# CNC-PowerSwitch-2016-v0_9.net
KiCad netlist of a schematic drawn in EAGLE
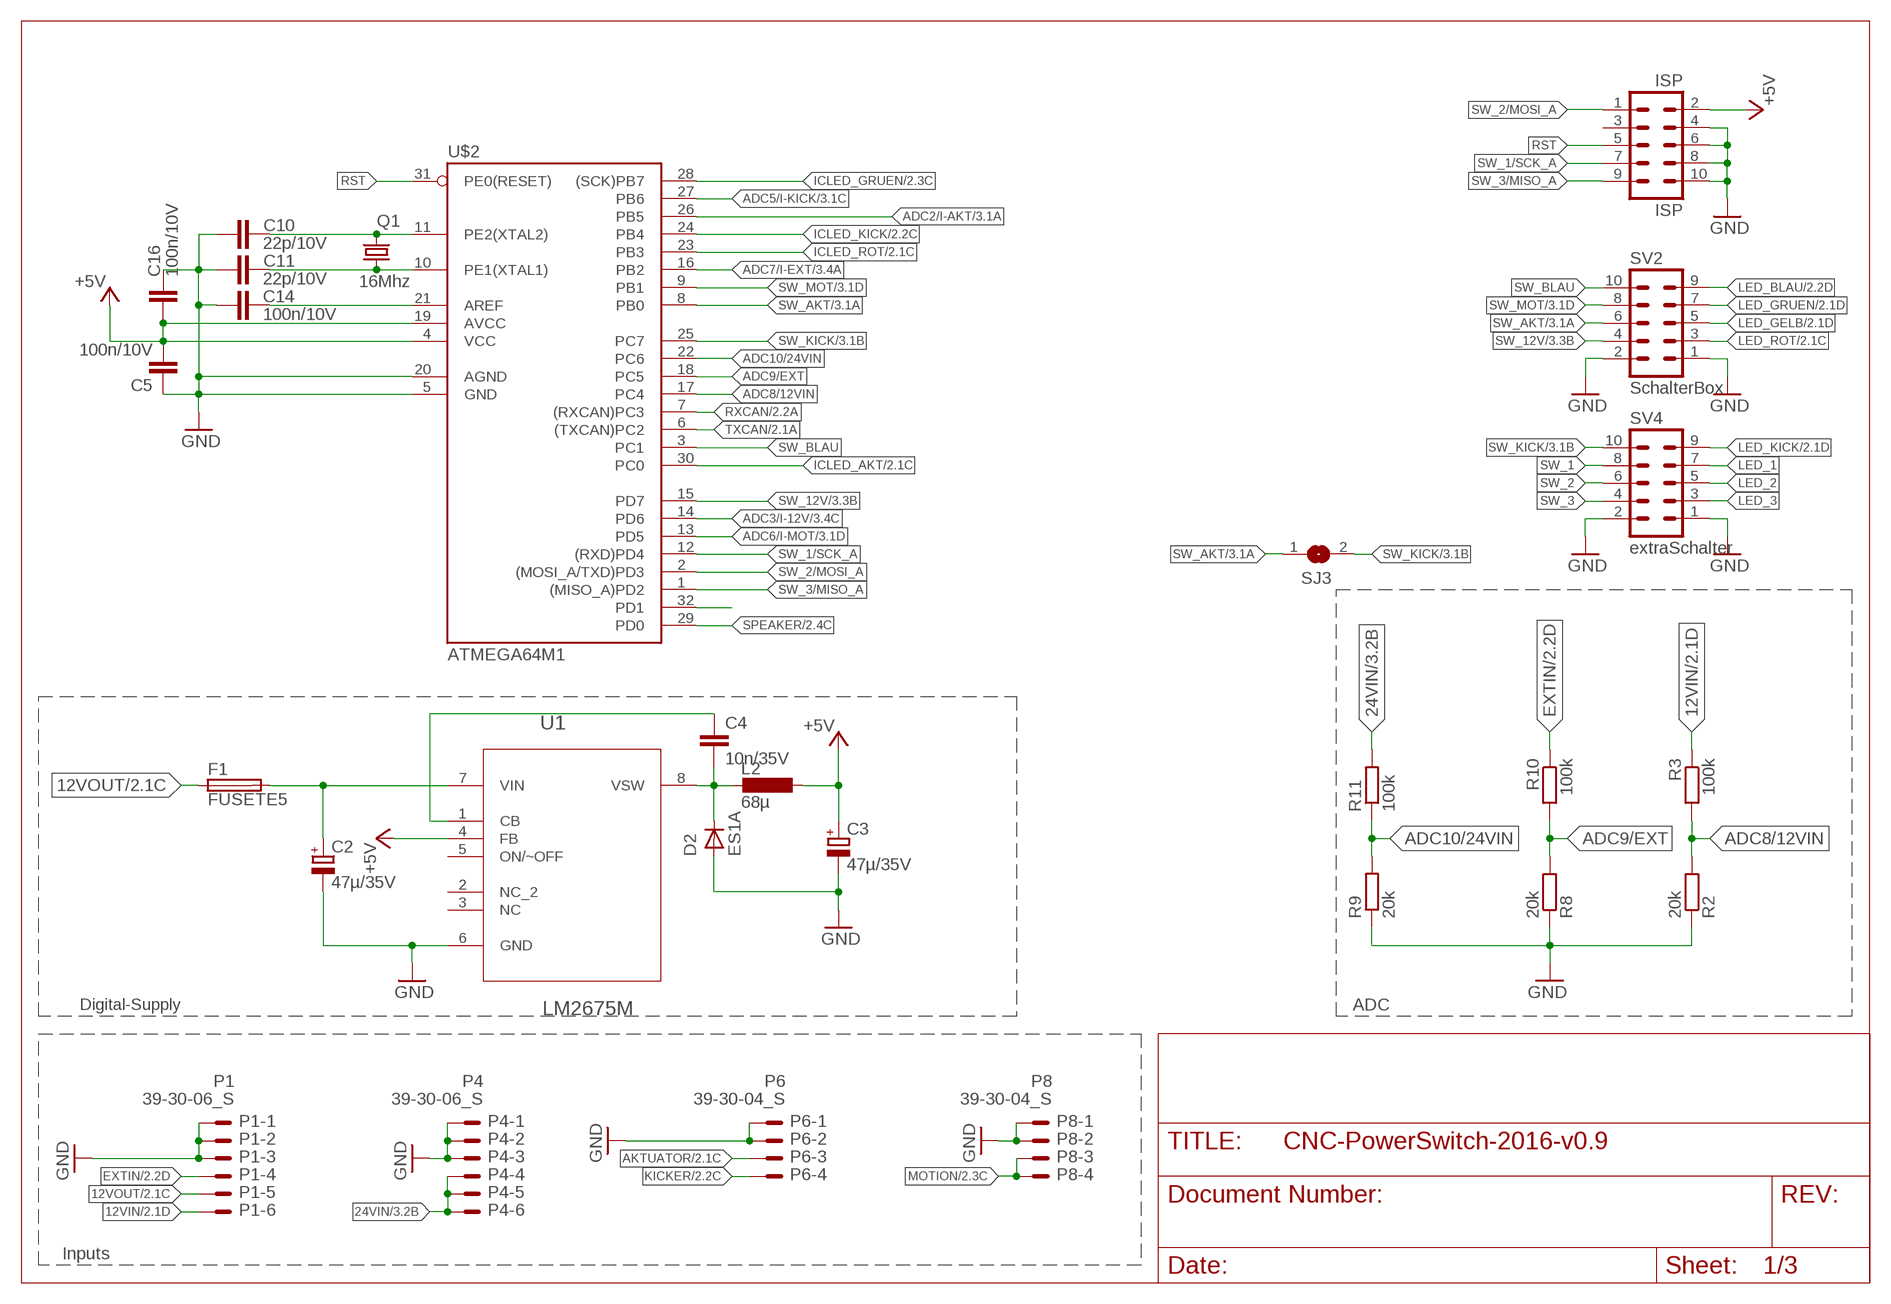
[diagram p0: schematic, sheet 1]
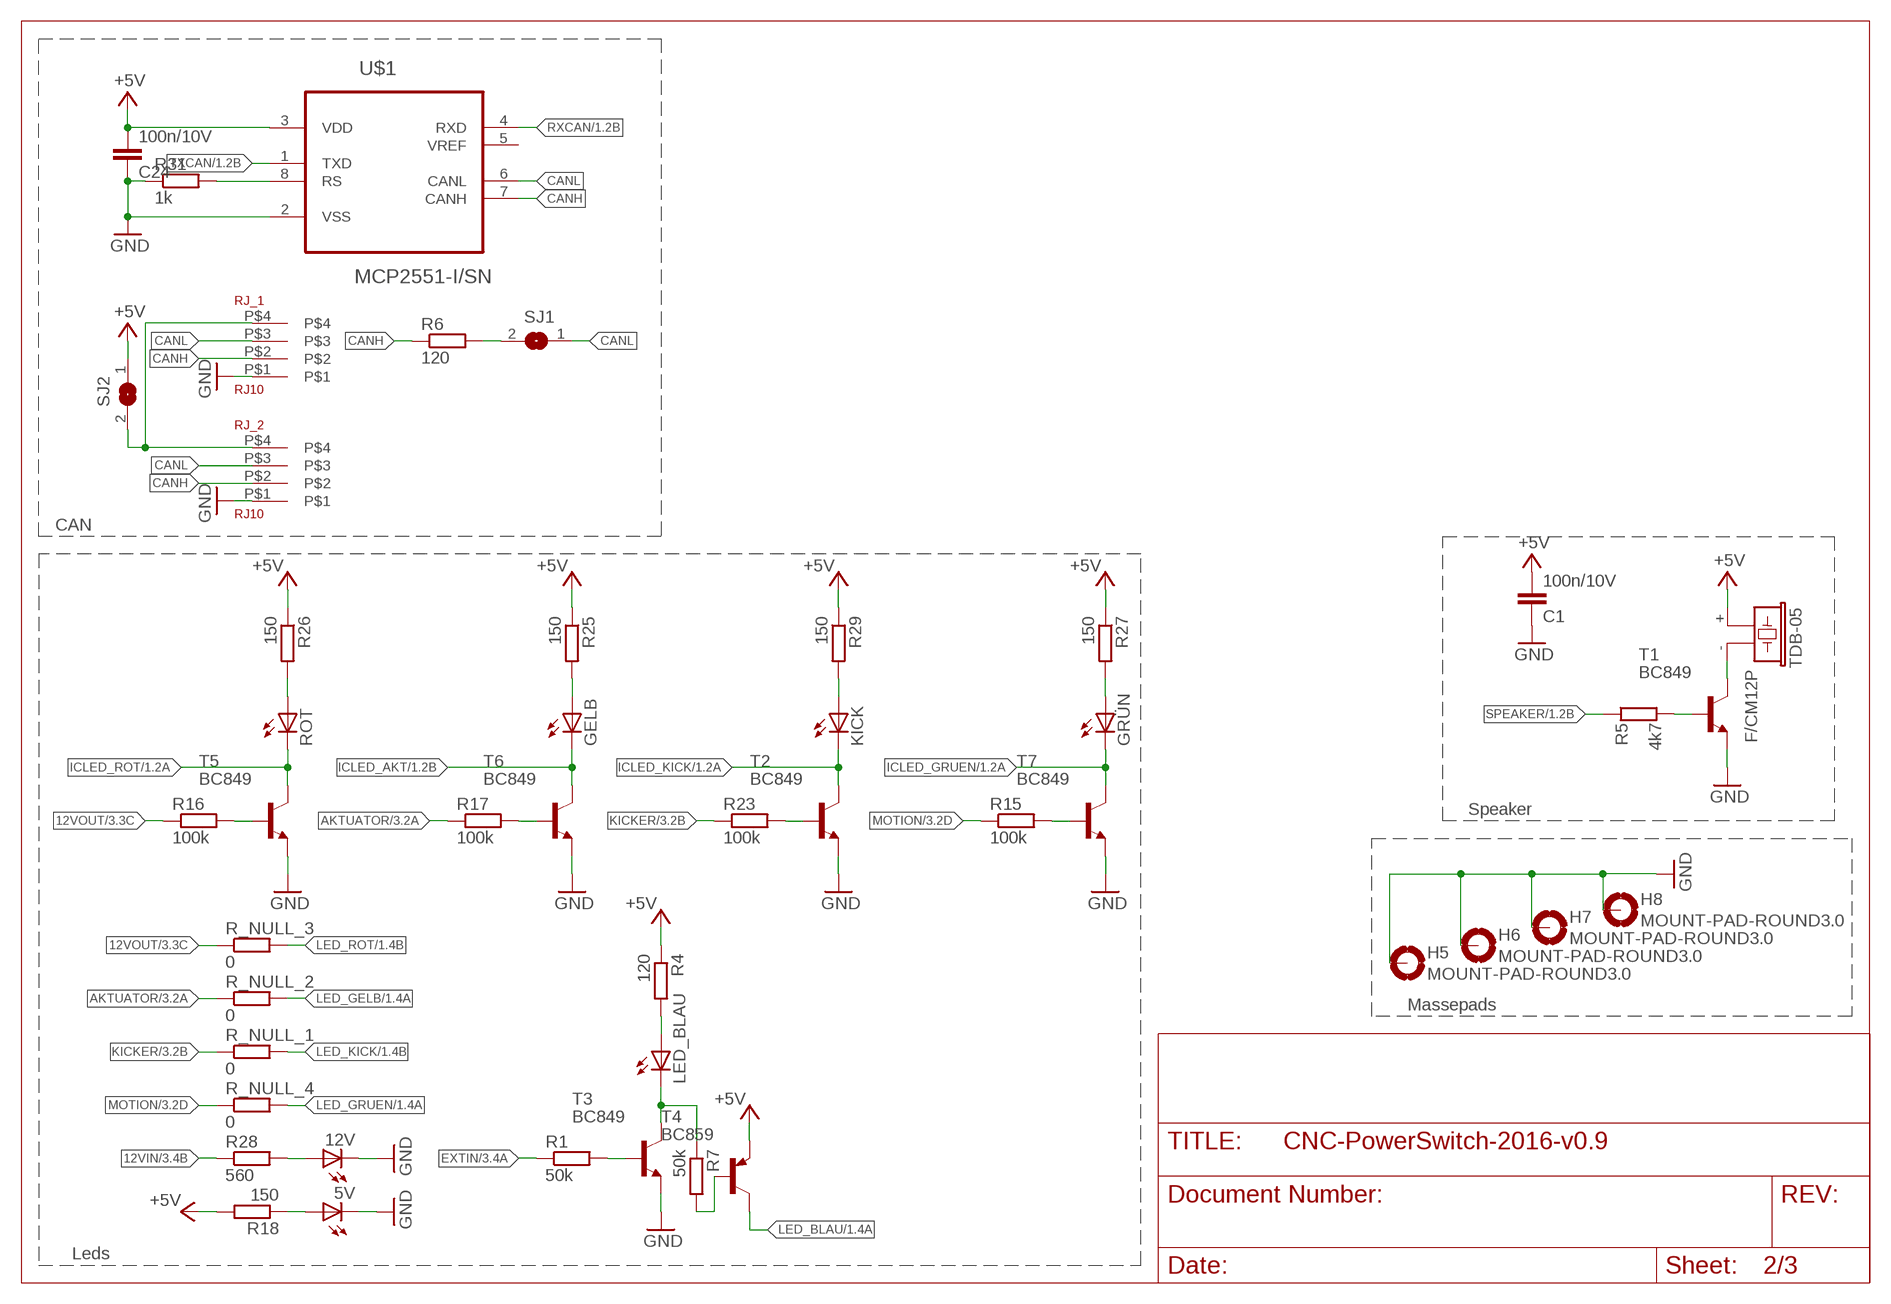
[diagram p1: schematic, sheet 2]
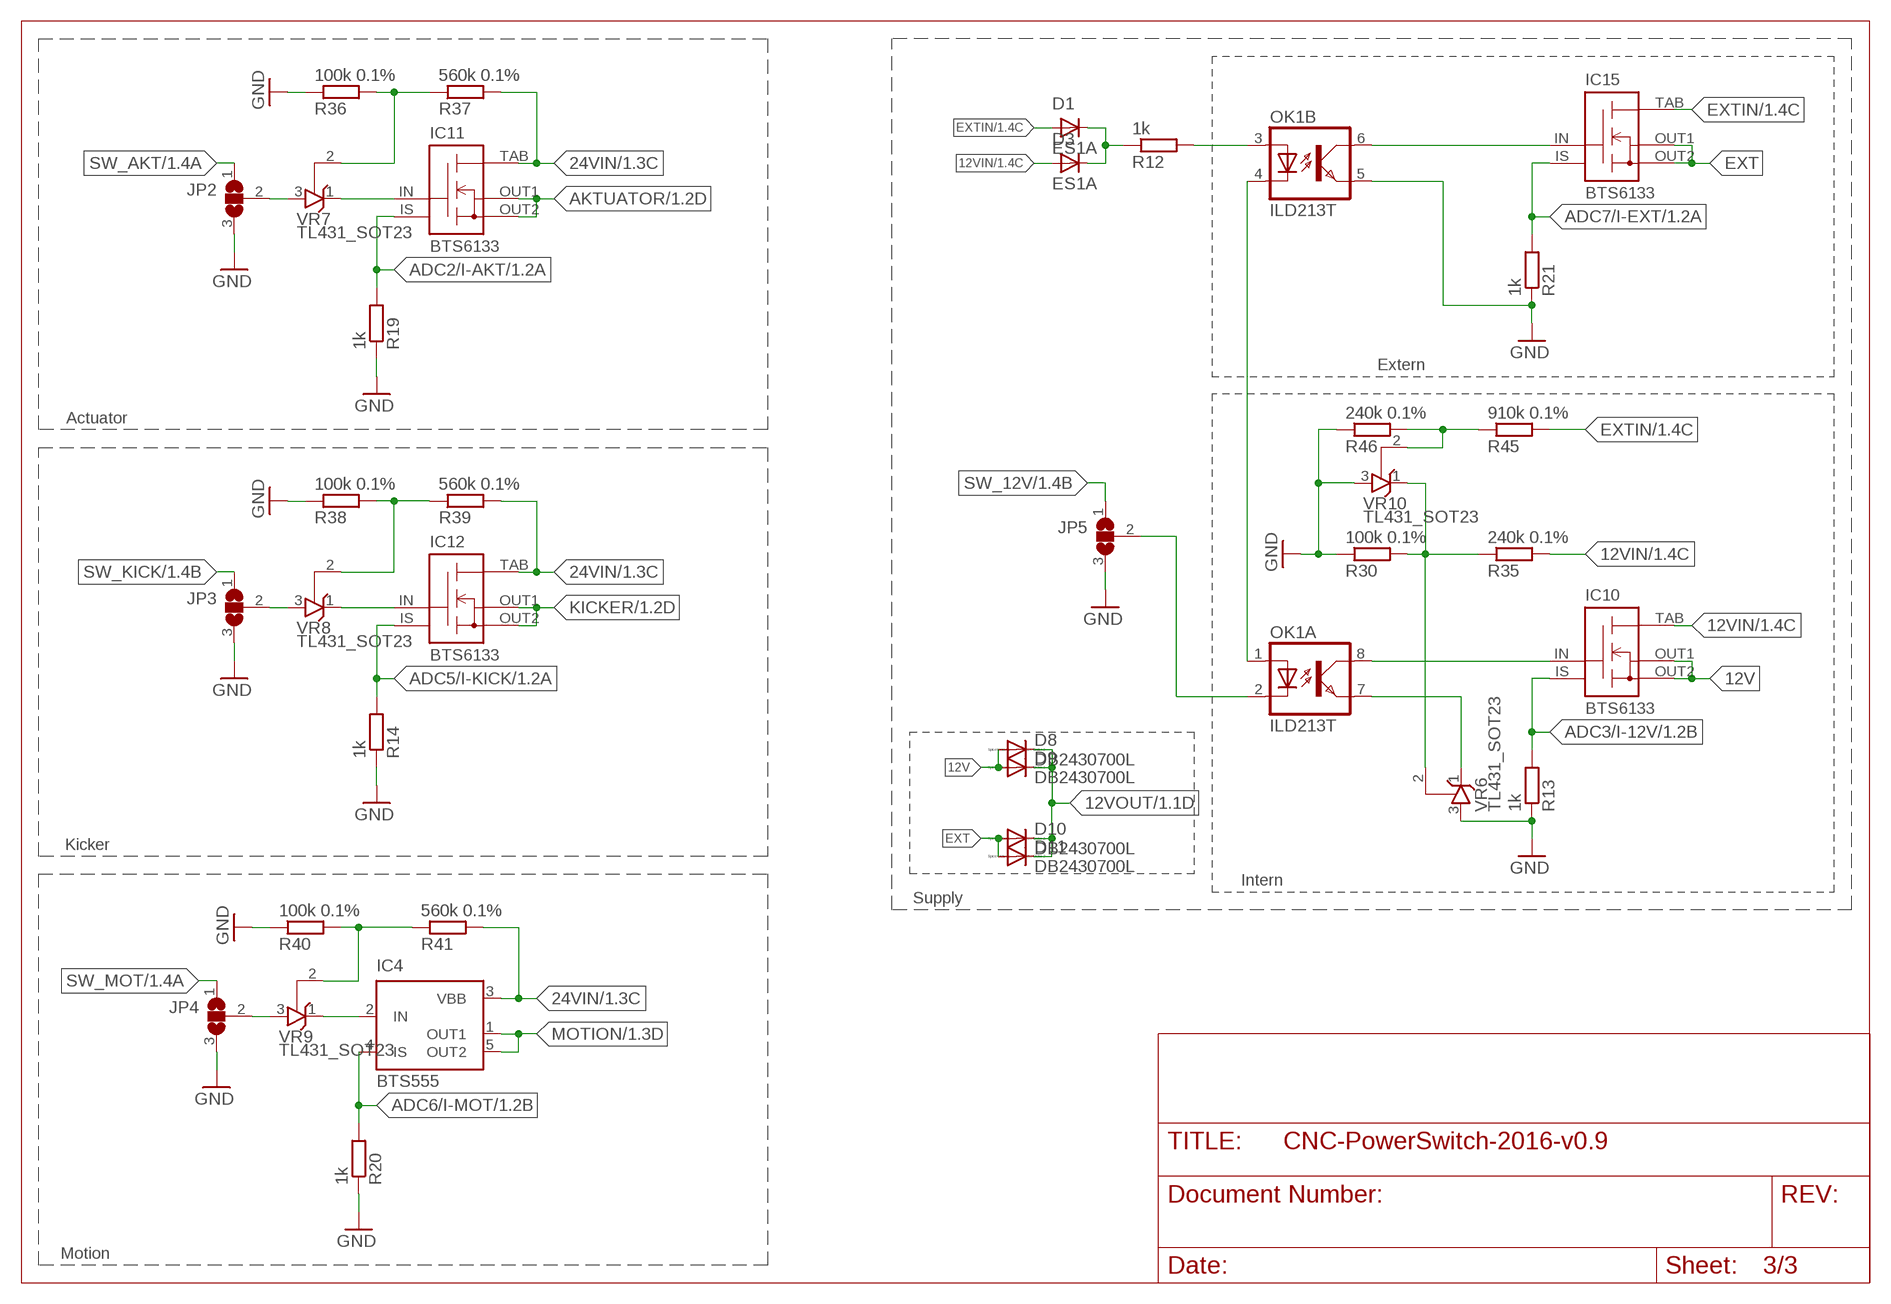
[diagram p2: schematic, sheet 3]

(export (version "E")
  (design (tool "Eeschema 10.0.6"))
  (components
    (comp (ref "D1")
      (value "ES1A")
      (footprint "eagle-import:SMA-DO214AC")
      (libsource (lib "eagle-import") (part "GF1"))
    )
    (comp (ref "D3")
      (value "ES1A")
      (footprint "eagle-import:SMA-DO214AC")
      (libsource (lib "eagle-import") (part "GF1"))
    )
    (comp (ref "D8")
      (value "DB2430700L")
      (footprint "eagle-import:TMINIP2-F2-B")
      (libsource (lib "eagle-import") (part "DB2430700L"))
    )
    (comp (ref "D9")
      (value "DB2430700L")
      (footprint "eagle-import:TMINIP2-F2-B")
      (libsource (lib "eagle-import") (part "DB2430700L"))
    )
    (comp (ref "D10")
      (value "DB2430700L")
      (footprint "eagle-import:TMINIP2-F2-B")
      (libsource (lib "eagle-import") (part "DB2430700L"))
    )
    (comp (ref "D11")
      (value "DB2430700L")
      (footprint "eagle-import:TMINIP2-F2-B")
      (libsource (lib "eagle-import") (part "DB2430700L"))
    )
    (comp (ref "IC4")
      (value "BTS555")
      (footprint "eagle-import:TO220-51")
      (fields (field (name "MF") "FARNELL") (field (name "MPN") "BTS555."))
      (libsource (lib "eagle-import") (part "BTS555"))
    )
    (comp (ref "IC10")
      (value "BTS6133")
      (footprint "eagle-import:TO252-51")
      (libsource (lib "eagle-import") (part "BTS6133"))
    )
    (comp (ref "IC11")
      (value "BTS6133")
      (footprint "eagle-import:TO252-51")
      (libsource (lib "eagle-import") (part "BTS6133"))
    )
    (comp (ref "IC12")
      (value "BTS6133")
      (footprint "eagle-import:TO252-51")
      (libsource (lib "eagle-import") (part "BTS6133"))
    )
    (comp (ref "IC15")
      (value "BTS6133")
      (footprint "eagle-import:TO252-51")
      (libsource (lib "eagle-import") (part "BTS6133"))
    )
    (comp (ref "JP2")
      (value "SJ2W")
      (footprint "eagle-import:SJ_2")
      (libsource (lib "eagle-import") (part "SJ2W"))
    )
    (comp (ref "JP3")
      (value "SJ2W")
      (footprint "eagle-import:SJ_2")
      (libsource (lib "eagle-import") (part "SJ2W"))
    )
    (comp (ref "JP4")
      (value "SJ2W")
      (footprint "eagle-import:SJ_2")
      (libsource (lib "eagle-import") (part "SJ2W"))
    )
    (comp (ref "JP5")
      (value "SJ2W")
      (footprint "eagle-import:SJ_2")
      (libsource (lib "eagle-import") (part "SJ2W"))
    )
    (comp (ref "OK1")
      (value "ILD213T")
      (footprint "eagle-import:SOIC08")
      (fields (field (name "MF") "VISHAY/TELEFUNKEN") (field (name "MPN") "ILD207T"))
      (libsource (lib "eagle-import") (part "ILD207"))
    )
    (comp (ref "R12")
      (value "1k")
      (footprint "eagle-import:R0805")
      (libsource (lib "eagle-import") (part "R-EU_R0805"))
    )
    (comp (ref "R13")
      (value "1k")
      (footprint "eagle-import:R0805")
      (libsource (lib "eagle-import") (part "R-EU_R0805"))
    )
    (comp (ref "R14")
      (value "1k")
      (footprint "eagle-import:R0805")
      (libsource (lib "eagle-import") (part "R-EU_R0805"))
    )
    (comp (ref "R19")
      (value "1k")
      (footprint "eagle-import:R0805")
      (libsource (lib "eagle-import") (part "R-EU_R0805"))
    )
    (comp (ref "R20")
      (value "1k")
      (footprint "eagle-import:R0805")
      (libsource (lib "eagle-import") (part "R-EU_R0805"))
    )
    (comp (ref "R21")
      (value "1k")
      (footprint "eagle-import:R0805")
      (libsource (lib "eagle-import") (part "R-EU_R0805"))
    )
    (comp (ref "R30")
      (value "100k 0.1%")
      (footprint "eagle-import:R0805")
      (libsource (lib "eagle-import") (part "R-EU_R0805"))
    )
    (comp (ref "R35")
      (value "240k 0.1%")
      (footprint "eagle-import:R0805")
      (libsource (lib "eagle-import") (part "R-EU_R0805"))
    )
    (comp (ref "R36")
      (value "100k 0.1%")
      (footprint "eagle-import:R0805")
      (libsource (lib "eagle-import") (part "R-EU_R0805"))
    )
    (comp (ref "R37")
      (value "560k 0.1%")
      (footprint "eagle-import:R0805")
      (libsource (lib "eagle-import") (part "R-EU_R0805"))
    )
    (comp (ref "R38")
      (value "100k 0.1%")
      (footprint "eagle-import:R0805")
      (libsource (lib "eagle-import") (part "R-EU_R0805"))
    )
    (comp (ref "R39")
      (value "560k 0.1%")
      (footprint "eagle-import:R0805")
      (libsource (lib "eagle-import") (part "R-EU_R0805"))
    )
    (comp (ref "R40")
      (value "100k 0.1%")
      (footprint "eagle-import:R0805")
      (libsource (lib "eagle-import") (part "R-EU_R0805"))
    )
    (comp (ref "R41")
      (value "560k 0.1%")
      (footprint "eagle-import:R0805")
      (libsource (lib "eagle-import") (part "R-EU_R0805"))
    )
    (comp (ref "R45")
      (value "910k 0.1%")
      (footprint "eagle-import:R0805")
      (libsource (lib "eagle-import") (part "R-EU_R0805"))
    )
    (comp (ref "R46")
      (value "240k 0.1%")
      (footprint "eagle-import:R0805")
      (libsource (lib "eagle-import") (part "R-EU_R0805"))
    )
    (comp (ref "VR6")
      (value "TL431_SOT23")
      (footprint "eagle-import:SOT23")
      (libsource (lib "eagle-import") (part "TL431_SOT23"))
    )
    (comp (ref "VR7")
      (value "TL431_SOT23")
      (footprint "eagle-import:SOT23")
      (libsource (lib "eagle-import") (part "TL431_SOT23"))
    )
    (comp (ref "VR8")
      (value "TL431_SOT23")
      (footprint "eagle-import:SOT23")
      (libsource (lib "eagle-import") (part "TL431_SOT23"))
    )
    (comp (ref "VR9")
      (value "TL431_SOT23")
      (footprint "eagle-import:SOT23")
      (libsource (lib "eagle-import") (part "TL431_SOT23"))
    )
    (comp (ref "VR10")
      (value "TL431_SOT23")
      (footprint "eagle-import:SOT23")
      (libsource (lib "eagle-import") (part "TL431_SOT23"))
    )
    (comp (ref "5V")
      (value "LEDCHIPLED_0805")
      (footprint "eagle-import:CHIPLED_0805")
      (libsource (lib "eagle-import") (part "LEDCHIPLED_0805"))
    )
    (comp (ref "12V")
      (value "LEDCHIPLED_0805")
      (footprint "eagle-import:CHIPLED_0805")
      (libsource (lib "eagle-import") (part "LEDCHIPLED_0805"))
    )
    (comp (ref "C1")
      (value "100n/10V")
      (footprint "eagle-import:C0603")
      (libsource (lib "eagle-import") (part "C-EUC0603"))
    )
    (comp (ref "C24")
      (value "100n/10V")
      (footprint "eagle-import:C0603")
      (libsource (lib "eagle-import") (part "C-EUC0603"))
    )
    (comp (ref "GELB")
      (value "LEDCHIPLED_0805")
      (footprint "eagle-import:CHIPLED_0805")
      (libsource (lib "eagle-import") (part "LEDCHIPLED_0805"))
    )
    (comp (ref "GRÜN")
      (value "LEDCHIPLED_0805")
      (footprint "eagle-import:CHIPLED_0805")
      (libsource (lib "eagle-import") (part "LEDCHIPLED_0805"))
    )
    (comp (ref "H5")
      (value "MOUNT-PAD-ROUND3.0")
      (footprint "eagle-import:3,0-PAD")
      (libsource (lib "eagle-import") (part "MOUNT-PAD-ROUND3.0"))
    )
    (comp (ref "H6")
      (value "MOUNT-PAD-ROUND3.0")
      (footprint "eagle-import:3,0-PAD")
      (libsource (lib "eagle-import") (part "MOUNT-PAD-ROUND3.0"))
    )
    (comp (ref "H7")
      (value "MOUNT-PAD-ROUND3.0")
      (footprint "eagle-import:3,0-PAD")
      (libsource (lib "eagle-import") (part "MOUNT-PAD-ROUND3.0"))
    )
    (comp (ref "H8")
      (value "MOUNT-PAD-ROUND3.0")
      (footprint "eagle-import:3,0-PAD")
      (libsource (lib "eagle-import") (part "MOUNT-PAD-ROUND3.0"))
    )
    (comp (ref "KICK")
      (value "LEDCHIPLED_0805")
      (footprint "eagle-import:CHIPLED_0805")
      (libsource (lib "eagle-import") (part "LEDCHIPLED_0805"))
    )
    (comp (ref "LED_BLAU")
      (value "LEDCHIPLED_0805")
      (footprint "eagle-import:CHIPLED_0805")
      (libsource (lib "eagle-import") (part "LEDCHIPLED_0805"))
    )
    (comp (ref "R1")
      (value "50k")
      (footprint "eagle-import:R0805")
      (libsource (lib "eagle-import") (part "R-EU_R0805"))
    )
    (comp (ref "R4")
      (value "120")
      (footprint "eagle-import:R0805")
      (libsource (lib "eagle-import") (part "R-EU_R0805"))
    )
    (comp (ref "R5")
      (value "4k7")
      (footprint "eagle-import:R0805")
      (libsource (lib "eagle-import") (part "R-EU_R0805"))
    )
    (comp (ref "R6")
      (value "120")
      (footprint "eagle-import:M0805")
      (libsource (lib "eagle-import") (part "R-EU_M0805"))
    )
    (comp (ref "R7")
      (value "50k")
      (footprint "eagle-import:R0805")
      (libsource (lib "eagle-import") (part "R-EU_R0805"))
    )
    (comp (ref "R15")
      (value "100k")
      (footprint "eagle-import:R0805")
      (libsource (lib "eagle-import") (part "R-EU_R0805"))
    )
    (comp (ref "R16")
      (value "100k")
      (footprint "eagle-import:R0805")
      (libsource (lib "eagle-import") (part "R-EU_R0805"))
    )
    (comp (ref "R17")
      (value "100k")
      (footprint "eagle-import:R0805")
      (libsource (lib "eagle-import") (part "R-EU_R0805"))
    )
    (comp (ref "R18")
      (value "150")
      (footprint "eagle-import:R0805")
      (libsource (lib "eagle-import") (part "R-EU_R0805"))
    )
    (comp (ref "R23")
      (value "100k")
      (footprint "eagle-import:R0805")
      (libsource (lib "eagle-import") (part "R-EU_R0805"))
    )
    (comp (ref "R25")
      (value "150")
      (footprint "eagle-import:R0805")
      (libsource (lib "eagle-import") (part "R-EU_R0805"))
    )
    (comp (ref "R26")
      (value "150")
      (footprint "eagle-import:R0805")
      (libsource (lib "eagle-import") (part "R-EU_R0805"))
    )
    (comp (ref "R27")
      (value "150")
      (footprint "eagle-import:R0805")
      (libsource (lib "eagle-import") (part "R-EU_R0805"))
    )
    (comp (ref "R28")
      (value "560")
      (footprint "eagle-import:R0805")
      (libsource (lib "eagle-import") (part "R-EU_R0805"))
    )
    (comp (ref "R29")
      (value "150")
      (footprint "eagle-import:R0805")
      (libsource (lib "eagle-import") (part "R-EU_R0805"))
    )
    (comp (ref "R31")
      (value "1k")
      (footprint "eagle-import:R0805")
      (libsource (lib "eagle-import") (part "R-EU_R0805"))
    )
    (comp (ref "RJ_1")
      (value "RJ10")
      (footprint "eagle-import:RJ10")
      (libsource (lib "eagle-import") (part "RJ10"))
    )
    (comp (ref "RJ_2")
      (value "RJ10")
      (footprint "eagle-import:RJ10")
      (libsource (lib "eagle-import") (part "RJ10"))
    )
    (comp (ref "ROT")
      (value "LEDCHIPLED_0805")
      (footprint "eagle-import:CHIPLED_0805")
      (libsource (lib "eagle-import") (part "LEDCHIPLED_0805"))
    )
    (comp (ref "R_NULL_1")
      (value "0")
      (footprint "eagle-import:R0402")
      (libsource (lib "eagle-import") (part "R-EU_R0402"))
    )
    (comp (ref "R_NULL_2")
      (value "0")
      (footprint "eagle-import:R0402")
      (libsource (lib "eagle-import") (part "R-EU_R0402"))
    )
    (comp (ref "R_NULL_3")
      (value "0")
      (footprint "eagle-import:R0402")
      (libsource (lib "eagle-import") (part "R-EU_R0402"))
    )
    (comp (ref "R_NULL_4")
      (value "0")
      (footprint "eagle-import:R0402")
      (libsource (lib "eagle-import") (part "R-EU_R0402"))
    )
    (comp (ref "SJ1") (value "SJ") (footprint "eagle-import:SJ") (libsource (lib "eagle-import") (part "SJ")))
    (comp (ref "SJ2") (value "SJ") (footprint "eagle-import:SJ") (libsource (lib "eagle-import") (part "SJ")))
    (comp (ref "T1")
      (value "BC849")
      (footprint "eagle-import:SOT23")
      (libsource (lib "eagle-import") (part "BC849"))
    )
    (comp (ref "T2")
      (value "BC849")
      (footprint "eagle-import:SOT23")
      (libsource (lib "eagle-import") (part "BC849"))
    )
    (comp (ref "T3")
      (value "BC849")
      (footprint "eagle-import:SOT23")
      (libsource (lib "eagle-import") (part "BC849"))
    )
    (comp (ref "T4")
      (value "BC859")
      (footprint "eagle-import:SOT23-BEC")
      (libsource (lib "eagle-import") (part "-PNP-SOT23-BECBC858C"))
    )
    (comp (ref "T5")
      (value "BC849")
      (footprint "eagle-import:SOT23")
      (libsource (lib "eagle-import") (part "BC849"))
    )
    (comp (ref "T6")
      (value "BC849")
      (footprint "eagle-import:SOT23")
      (libsource (lib "eagle-import") (part "BC849"))
    )
    (comp (ref "T7")
      (value "BC849")
      (footprint "eagle-import:SOT23")
      (libsource (lib "eagle-import") (part "BC849"))
    )
    (comp (ref "TDB-05")
      (value "F/CM12P")
      (footprint "eagle-import:F_CM12P")
      (libsource (lib "eagle-import") (part "F/CM12P"))
    )
    (comp (ref "U$1")
      (value "MCP2551-I/SN")
      (footprint "eagle-import:SOIC127P600X175-8N")
      (libsource (lib "eagle-import") (part "MCP2551-I/SN"))
    )
    (comp (ref "C2")
      (value "47µ/35V")
      (footprint "eagle-import:PANASONIC_D")
      (libsource (lib "eagle-import") (part "CPOL-EUD"))
    )
    (comp (ref "C3")
      (value "47µ/35V")
      (footprint "eagle-import:PANASONIC_D")
      (libsource (lib "eagle-import") (part "CPOL-EUD"))
    )
    (comp (ref "C4")
      (value "10n/35V")
      (footprint "eagle-import:C0603")
      (libsource (lib "eagle-import") (part "C-EUC0603"))
    )
    (comp (ref "C5")
      (value "100n/10V")
      (footprint "eagle-import:C0603")
      (libsource (lib "eagle-import") (part "C-EUC0603"))
    )
    (comp (ref "C10")
      (value "22p/10V")
      (footprint "eagle-import:C0603")
      (libsource (lib "eagle-import") (part "C-EUC0603"))
    )
    (comp (ref "C11")
      (value "22p/10V")
      (footprint "eagle-import:C0603")
      (libsource (lib "eagle-import") (part "C-EUC0603"))
    )
    (comp (ref "C14")
      (value "100n/10V")
      (footprint "eagle-import:C0603")
      (libsource (lib "eagle-import") (part "C-EUC0603"))
    )
    (comp (ref "C16")
      (value "100n/10V")
      (footprint "eagle-import:C0603")
      (libsource (lib "eagle-import") (part "C-EUC0603"))
    )
    (comp (ref "D2")
      (value "ES1A")
      (footprint "eagle-import:SMA-DO214AC")
      (libsource (lib "eagle-import") (part "GF1"))
    )
    (comp (ref "F1")
      (value "FUSETE5")
      (footprint "eagle-import:TE5")
      (libsource (lib "eagle-import") (part "FUSETE5"))
    )
    (comp (ref "ISP")
      (value "ISP")
      (footprint "eagle-import:ML10")
      (libsource (lib "eagle-import") (part "ML10"))
    )
    (comp (ref "L2")
      (value "68µ")
      (footprint "eagle-import:PISM")
      (libsource (lib "eagle-import") (part "L-EUPISM"))
    )
    (comp (ref "P1")
      (value "39-30-06_S")
      (footprint "eagle-import:39-30-_06_")
      (libsource (lib "eagle-import") (part "39-30-?06?_S"))
    )
    (comp (ref "P4")
      (value "39-30-06_S")
      (footprint "eagle-import:39-30-_06_")
      (libsource (lib "eagle-import") (part "39-30-?06?_S"))
    )
    (comp (ref "P6")
      (value "39-30-04_S")
      (footprint "eagle-import:39-30-_04_")
      (libsource (lib "eagle-import") (part "39-30-?04?_S"))
    )
    (comp (ref "P8")
      (value "39-30-04_S")
      (footprint "eagle-import:39-30-_04_")
      (libsource (lib "eagle-import") (part "39-30-?04?_S"))
    )
    (comp (ref "Q1")
      (value "16Mhz")
      (footprint "eagle-import:HC49UP")
      (libsource (lib "eagle-import") (part "CRYSTALHC49UP"))
    )
    (comp (ref "R2")
      (value "20k")
      (footprint "eagle-import:R0805")
      (libsource (lib "eagle-import") (part "R-EU_R0805"))
    )
    (comp (ref "R3")
      (value "100k")
      (footprint "eagle-import:R0805")
      (libsource (lib "eagle-import") (part "R-EU_R0805"))
    )
    (comp (ref "R8")
      (value "20k")
      (footprint "eagle-import:R0805")
      (libsource (lib "eagle-import") (part "R-EU_R0805"))
    )
    (comp (ref "R9")
      (value "20k")
      (footprint "eagle-import:R0805")
      (libsource (lib "eagle-import") (part "R-EU_R0805"))
    )
    (comp (ref "R10")
      (value "100k")
      (footprint "eagle-import:R0805")
      (libsource (lib "eagle-import") (part "R-EU_R0805"))
    )
    (comp (ref "R11")
      (value "100k")
      (footprint "eagle-import:R0805")
      (libsource (lib "eagle-import") (part "R-EU_R0805"))
    )
    (comp (ref "SJ3") (value "SJ") (footprint "eagle-import:SJ") (libsource (lib "eagle-import") (part "SJ")))
    (comp (ref "SV2")
      (value "SchalterBox")
      (footprint "eagle-import:ML10")
      (libsource (lib "eagle-import") (part "ML10"))
    )
    (comp (ref "SV4")
      (value "extraSchalter")
      (footprint "eagle-import:ML10")
      (libsource (lib "eagle-import") (part "ML10"))
    )
    (comp (ref "U$2")
      (value "ATMEGA64M1")
      (footprint "eagle-import:TQFP32-08")
      (libsource (lib "eagle-import") (part "ATMEGA64M1"))
    )
    (comp (ref "U1")
      (value "LM2675M")
      (footprint "eagle-import:SOIC127P620X175-8N")
      (fields (field (name "MPN") "LM2675M-3.3"))
      (libsource (lib "eagle-import") (part "LM2675M-3.3"))
    )
  )
  (nets
    (net (code "1") (name "+5V") (class "Default")
      (node (ref "C1") (pin "2") (pinfunction "2_2") (pintype "passive"))
      (node (ref "C16") (pin "1") (pinfunction "1_1") (pintype "passive"))
      (node (ref "C24") (pin "2") (pinfunction "2_2") (pintype "passive"))
      (node (ref "C3") (pin "+") (pinfunction "+_+") (pintype "passive"))
      (node (ref "C5") (pin "2") (pinfunction "2_2") (pintype "passive"))
      (node (ref "ISP") (pin "2") (pinfunction "2_2") (pintype "passive"))
      (node (ref "L2") (pin "1") (pinfunction "1_1") (pintype "passive"))
      (node (ref "R18") (pin "2") (pinfunction "2_2") (pintype "passive"))
      (node (ref "R25") (pin "1") (pinfunction "1_1") (pintype "passive"))
      (node (ref "R26") (pin "1") (pinfunction "1_1") (pintype "passive"))
      (node (ref "R27") (pin "1") (pinfunction "1_1") (pintype "passive"))
      (node (ref "R29") (pin "1") (pinfunction "1_1") (pintype "passive"))
      (node (ref "R4") (pin "1") (pinfunction "1_1") (pintype "passive"))
      (node (ref "SJ2") (pin "1") (pinfunction "1_1") (pintype "passive"))
      (node (ref "T4") (pin "E") (pinfunction "E_E") (pintype "passive"))
      (node (ref "TDB-05") (pin "+") (pinfunction "1_+") (pintype "passive"))
      (node (ref "U$1") (pin "3") (pinfunction "VDD_3") (pintype "power_in"))
      (node (ref "U$2") (pin "19") (pinfunction "AVCC_19") (pintype "bidirectional"))
      (node (ref "U$2") (pin "4") (pinfunction "VCC_4") (pintype "bidirectional"))
      (node (ref "U1") (pin "4") (pinfunction "FB_4") (pintype "input"))
    )
    (net (code "2") (name "12V") (class "Default")
      (node (ref "D8") (pin "A") (pinfunction "A_A") (pintype "passive"))
      (node (ref "D9") (pin "A") (pinfunction "A_A") (pintype "passive"))
      (node (ref "IC10") (pin "OUT1") (pinfunction "OUT_OUT1") (pintype "passive"))
      (node (ref "IC10") (pin "OUT2") (pinfunction "OUT_OUT2") (pintype "passive"))
    )
    (net (code "3") (name "12VIN") (class "Default")
      (node (ref "D3") (pin "A") (pinfunction "A_A") (pintype "passive"))
      (node (ref "IC10") (pin "TAB") (pinfunction "VBB_TAB") (pintype "power_in"))
      (node (ref "P1") (pin "6") (pinfunction "P_6") (pintype "passive"))
      (node (ref "R28") (pin "1") (pinfunction "1_1") (pintype "passive"))
      (node (ref "R3") (pin "1") (pinfunction "1_1") (pintype "passive"))
      (node (ref "R35") (pin "2") (pinfunction "2_2") (pintype "passive"))
    )
    (net (code "4") (name "12VOUT") (class "Default")
      (node (ref "D10") (pin "C") (pinfunction "C_C") (pintype "passive"))
      (node (ref "D11") (pin "C") (pinfunction "C_C") (pintype "passive"))
      (node (ref "D8") (pin "C") (pinfunction "C_C") (pintype "passive"))
      (node (ref "D9") (pin "C") (pinfunction "C_C") (pintype "passive"))
      (node (ref "F1") (pin "1") (pinfunction "1_1") (pintype "passive"))
      (node (ref "P1") (pin "5") (pinfunction "P_5") (pintype "passive"))
      (node (ref "R16") (pin "1") (pinfunction "1_1") (pintype "passive"))
      (node (ref "R_NULL_3") (pin "1") (pinfunction "1_1") (pintype "passive"))
    )
    (net (code "5") (name "24VIN") (class "Default")
      (node (ref "IC11") (pin "TAB") (pinfunction "VBB_TAB") (pintype "power_in"))
      (node (ref "IC12") (pin "TAB") (pinfunction "VBB_TAB") (pintype "power_in"))
      (node (ref "IC4") (pin "3") (pinfunction "VBB_3") (pintype "passive"))
      (node (ref "P4") (pin "4") (pinfunction "P_4") (pintype "passive"))
      (node (ref "P4") (pin "5") (pinfunction "P_5") (pintype "passive"))
      (node (ref "P4") (pin "6") (pinfunction "P_6") (pintype "passive"))
      (node (ref "R11") (pin "2") (pinfunction "2_2") (pintype "passive"))
      (node (ref "R37") (pin "2") (pinfunction "2_2") (pintype "passive"))
      (node (ref "R39") (pin "2") (pinfunction "2_2") (pintype "passive"))
      (node (ref "R41") (pin "2") (pinfunction "2_2") (pintype "passive"))
    )
    (net (code "6") (name "ADC2{slash}I-AKT") (class "Default")
      (node (ref "IC11") (pin "IS") (pinfunction "IS_IS") (pintype "passive"))
      (node (ref "R19") (pin "2") (pinfunction "2_2") (pintype "passive"))
      (node (ref "U$2") (pin "26") (pinfunction "PB5_26") (pintype "bidirectional"))
    )
    (net (code "7") (name "ADC3{slash}I-12V") (class "Default")
      (node (ref "IC10") (pin "IS") (pinfunction "IS_IS") (pintype "passive"))
      (node (ref "R13") (pin "2") (pinfunction "2_2") (pintype "passive"))
      (node (ref "U$2") (pin "14") (pinfunction "PD6_14") (pintype "bidirectional"))
    )
    (net (code "8") (name "ADC5{slash}I-KICK") (class "Default")
      (node (ref "IC12") (pin "IS") (pinfunction "IS_IS") (pintype "passive"))
      (node (ref "R14") (pin "2") (pinfunction "2_2") (pintype "passive"))
      (node (ref "U$2") (pin "27") (pinfunction "PB6_27") (pintype "bidirectional"))
    )
    (net (code "9") (name "ADC6{slash}I-MOT") (class "Default")
      (node (ref "IC4") (pin "4") (pinfunction "IS_4") (pintype "passive"))
      (node (ref "R20") (pin "2") (pinfunction "2_2") (pintype "passive"))
      (node (ref "U$2") (pin "13") (pinfunction "PD5_13") (pintype "bidirectional"))
    )
    (net (code "10") (name "ADC7{slash}I-EXT") (class "Default")
      (node (ref "IC15") (pin "IS") (pinfunction "IS_IS") (pintype "passive"))
      (node (ref "R21") (pin "2") (pinfunction "2_2") (pintype "passive"))
      (node (ref "U$2") (pin "16") (pinfunction "PB2_16") (pintype "bidirectional"))
    )
    (net (code "11") (name "ADC8{slash}12VIN") (class "Default")
      (node (ref "R2") (pin "2") (pinfunction "2_2") (pintype "passive"))
      (node (ref "R3") (pin "2") (pinfunction "2_2") (pintype "passive"))
      (node (ref "U$2") (pin "17") (pinfunction "PC4_17") (pintype "bidirectional"))
    )
    (net (code "12") (name "ADC9{slash}EXT") (class "Default")
      (node (ref "R10") (pin "2") (pinfunction "2_2") (pintype "passive"))
      (node (ref "R8") (pin "2") (pinfunction "2_2") (pintype "passive"))
      (node (ref "U$2") (pin "18") (pinfunction "PC5_18") (pintype "bidirectional"))
    )
    (net (code "13") (name "ADC10{slash}24VIN") (class "Default")
      (node (ref "R11") (pin "1") (pinfunction "1_1") (pintype "passive"))
      (node (ref "R9") (pin "2") (pinfunction "2_2") (pintype "passive"))
      (node (ref "U$2") (pin "22") (pinfunction "PC6_22") (pintype "bidirectional"))
    )
    (net (code "14") (name "AKTUATOR") (class "Default")
      (node (ref "IC11") (pin "OUT1") (pinfunction "OUT_OUT1") (pintype "passive"))
      (node (ref "IC11") (pin "OUT2") (pinfunction "OUT_OUT2") (pintype "passive"))
      (node (ref "P6") (pin "3") (pinfunction "P_3") (pintype "passive"))
      (node (ref "R17") (pin "1") (pinfunction "1_1") (pintype "passive"))
      (node (ref "R_NULL_2") (pin "1") (pinfunction "1_1") (pintype "passive"))
    )
    (net (code "15") (name "CANH") (class "Default")
      (node (ref "R6") (pin "1") (pinfunction "1_1") (pintype "passive"))
      (node (ref "RJ_1") (pin "P$2") (pinfunction "P$2_P$2") (pintype "bidirectional"))
      (node (ref "RJ_2") (pin "P$2") (pinfunction "P$2_P$2") (pintype "bidirectional"))
      (node (ref "U$1") (pin "7") (pinfunction "CANH_7") (pintype "bidirectional"))
    )
    (net (code "16") (name "CANL") (class "Default")
      (node (ref "RJ_1") (pin "P$3") (pinfunction "P$3_P$3") (pintype "bidirectional"))
      (node (ref "RJ_2") (pin "P$3") (pinfunction "P$3_P$3") (pintype "bidirectional"))
      (node (ref "SJ1") (pin "1") (pinfunction "1_1") (pintype "passive"))
      (node (ref "U$1") (pin "6") (pinfunction "CANL_6") (pintype "bidirectional"))
    )
    (net (code "17") (name "EXT") (class "Default")
      (node (ref "D10") (pin "A") (pinfunction "A_A") (pintype "passive"))
      (node (ref "D11") (pin "A") (pinfunction "A_A") (pintype "passive"))
      (node (ref "IC15") (pin "OUT1") (pinfunction "OUT_OUT1") (pintype "passive"))
      (node (ref "IC15") (pin "OUT2") (pinfunction "OUT_OUT2") (pintype "passive"))
    )
    (net (code "18") (name "EXTIN") (class "Default")
      (node (ref "D1") (pin "A") (pinfunction "A_A") (pintype "passive"))
      (node (ref "IC15") (pin "TAB") (pinfunction "VBB_TAB") (pintype "power_in"))
      (node (ref "P1") (pin "4") (pinfunction "P_4") (pintype "passive"))
      (node (ref "R1") (pin "1") (pinfunction "1_1") (pintype "passive"))
      (node (ref "R10") (pin "1") (pinfunction "1_1") (pintype "passive"))
      (node (ref "R45") (pin "2") (pinfunction "2_2") (pintype "passive"))
    )
    (net (code "19") (name "GND") (class "Default")
      (node (ref "12V") (pin "C") (pinfunction "C_C") (pintype "passive"))
      (node (ref "5V") (pin "C") (pinfunction "C_C") (pintype "passive"))
      (node (ref "C1") (pin "1") (pinfunction "1_1") (pintype "passive"))
      (node (ref "C10") (pin "1") (pinfunction "1_1") (pintype "passive"))
      (node (ref "C11") (pin "1") (pinfunction "1_1") (pintype "passive"))
      (node (ref "C14") (pin "1") (pinfunction "1_1") (pintype "passive"))
      (node (ref "C16") (pin "2") (pinfunction "2_2") (pintype "passive"))
      (node (ref "C2") (pin "-") (pinfunction "-_-") (pintype "passive"))
      (node (ref "C24") (pin "1") (pinfunction "1_1") (pintype "passive"))
      (node (ref "C3") (pin "-") (pinfunction "-_-") (pintype "passive"))
      (node (ref "C5") (pin "1") (pinfunction "1_1") (pintype "passive"))
      (node (ref "D2") (pin "A") (pinfunction "A_A") (pintype "passive"))
      (node (ref "H5") (pin "B3,0") (pinfunction "MOUNT_B3,0") (pintype "passive"))
      (node (ref "H6") (pin "B3,0") (pinfunction "MOUNT_B3,0") (pintype "passive"))
      (node (ref "H7") (pin "B3,0") (pinfunction "MOUNT_B3,0") (pintype "passive"))
      (node (ref "H8") (pin "B3,0") (pinfunction "MOUNT_B3,0") (pintype "passive"))
      (node (ref "ISP") (pin "10") (pinfunction "10_10") (pintype "passive"))
      (node (ref "ISP") (pin "4") (pinfunction "4_4") (pintype "passive"))
      (node (ref "ISP") (pin "6") (pinfunction "6_6") (pintype "passive"))
      (node (ref "ISP") (pin "8") (pinfunction "8_8") (pintype "passive"))
      (node (ref "JP2") (pin "3") (pinfunction "3_3") (pintype "passive"))
      (node (ref "JP3") (pin "3") (pinfunction "3_3") (pintype "passive"))
      (node (ref "JP4") (pin "3") (pinfunction "3_3") (pintype "passive"))
      (node (ref "JP5") (pin "3") (pinfunction "3_3") (pintype "passive"))
      (node (ref "OK1") (pin "5") (pinfunction "EMIT_5") (pintype "passive"))
      (node (ref "P1") (pin "1") (pinfunction "P_1") (pintype "passive"))
      (node (ref "P1") (pin "2") (pinfunction "P_2") (pintype "passive"))
      (node (ref "P1") (pin "3") (pinfunction "P_3") (pintype "passive"))
      (node (ref "P4") (pin "1") (pinfunction "P_1") (pintype "passive"))
      (node (ref "P4") (pin "2") (pinfunction "P_2") (pintype "passive"))
      (node (ref "P4") (pin "3") (pinfunction "P_3") (pintype "passive"))
      (node (ref "P6") (pin "1") (pinfunction "P_1") (pintype "passive"))
      (node (ref "P6") (pin "2") (pinfunction "P_2") (pintype "passive"))
      (node (ref "P8") (pin "1") (pinfunction "P_1") (pintype "passive"))
      (node (ref "P8") (pin "2") (pinfunction "P_2") (pintype "passive"))
      (node (ref "R13") (pin "1") (pinfunction "1_1") (pintype "passive"))
      (node (ref "R14") (pin "1") (pinfunction "1_1") (pintype "passive"))
      (node (ref "R19") (pin "1") (pinfunction "1_1") (pintype "passive"))
      (node (ref "R2") (pin "1") (pinfunction "1_1") (pintype "passive"))
      (node (ref "R20") (pin "1") (pinfunction "1_1") (pintype "passive"))
      (node (ref "R21") (pin "1") (pinfunction "1_1") (pintype "passive"))
      (node (ref "R30") (pin "1") (pinfunction "1_1") (pintype "passive"))
      (node (ref "R31") (pin "1") (pinfunction "1_1") (pintype "passive"))
      (node (ref "R36") (pin "1") (pinfunction "1_1") (pintype "passive"))
      (node (ref "R38") (pin "1") (pinfunction "1_1") (pintype "passive"))
      (node (ref "R40") (pin "1") (pinfunction "1_1") (pintype "passive"))
      (node (ref "R46") (pin "1") (pinfunction "1_1") (pintype "passive"))
      (node (ref "R8") (pin "1") (pinfunction "1_1") (pintype "passive"))
      (node (ref "R9") (pin "1") (pinfunction "1_1") (pintype "passive"))
      (node (ref "RJ_1") (pin "P$1") (pinfunction "P$1_P$1") (pintype "bidirectional"))
      (node (ref "RJ_2") (pin "P$1") (pinfunction "P$1_P$1") (pintype "bidirectional"))
      (node (ref "SV2") (pin "1") (pinfunction "1_1") (pintype "passive"))
      (node (ref "SV2") (pin "2") (pinfunction "2_2") (pintype "passive"))
      (node (ref "SV4") (pin "1") (pinfunction "1_1") (pintype "passive"))
      (node (ref "SV4") (pin "2") (pinfunction "2_2") (pintype "passive"))
      (node (ref "T1") (pin "2") (pinfunction "E_2") (pintype "passive"))
      (node (ref "T2") (pin "2") (pinfunction "E_2") (pintype "passive"))
      (node (ref "T3") (pin "2") (pinfunction "E_2") (pintype "passive"))
      (node (ref "T5") (pin "2") (pinfunction "E_2") (pintype "passive"))
      (node (ref "T6") (pin "2") (pinfunction "E_2") (pintype "passive"))
      (node (ref "T7") (pin "2") (pinfunction "E_2") (pintype "passive"))
      (node (ref "U$1") (pin "2") (pinfunction "VSS_2") (pintype "passive"))
      (node (ref "U$2") (pin "20") (pinfunction "AGND_20") (pintype "power_in"))
      (node (ref "U$2") (pin "5") (pinfunction "GND_5") (pintype "power_in"))
      (node (ref "U1") (pin "6") (pinfunction "GND_6") (pintype "passive"))
      (node (ref "VR10") (pin "3") (pinfunction "A_3") (pintype "passive"))
      (node (ref "VR6") (pin "3") (pinfunction "A_3") (pintype "passive"))
    )
    (net (code "20") (name "ICLED_AKT") (class "Default")
      (node (ref "GELB") (pin "C") (pinfunction "C_C") (pintype "passive"))
      (node (ref "T6") (pin "3") (pinfunction "C_3") (pintype "passive"))
      (node (ref "U$2") (pin "30") (pinfunction "PC0_30") (pintype "bidirectional"))
    )
    (net (code "21") (name "ICLED_GRUEN") (class "Default")
      (node (ref "GRÜN") (pin "C") (pinfunction "C_C") (pintype "passive"))
      (node (ref "T7") (pin "3") (pinfunction "C_3") (pintype "passive"))
      (node (ref "U$2") (pin "28") (pinfunction "(SCK)PB7_28") (pintype "bidirectional"))
    )
    (net (code "22") (name "ICLED_KICK") (class "Default")
      (node (ref "KICK") (pin "C") (pinfunction "C_C") (pintype "passive"))
      (node (ref "T2") (pin "3") (pinfunction "C_3") (pintype "passive"))
      (node (ref "U$2") (pin "24") (pinfunction "PB4_24") (pintype "bidirectional"))
    )
    (net (code "23") (name "ICLED_ROT") (class "Default")
      (node (ref "ROT") (pin "C") (pinfunction "C_C") (pintype "passive"))
      (node (ref "T5") (pin "3") (pinfunction "C_3") (pintype "passive"))
      (node (ref "U$2") (pin "23") (pinfunction "PB3_23") (pintype "bidirectional"))
    )
    (net (code "24") (name "KICKER") (class "Default")
      (node (ref "IC12") (pin "OUT1") (pinfunction "OUT_OUT1") (pintype "passive"))
      (node (ref "IC12") (pin "OUT2") (pinfunction "OUT_OUT2") (pintype "passive"))
      (node (ref "P6") (pin "4") (pinfunction "P_4") (pintype "passive"))
      (node (ref "R23") (pin "1") (pinfunction "1_1") (pintype "passive"))
      (node (ref "R_NULL_1") (pin "1") (pinfunction "1_1") (pintype "passive"))
    )
    (net (code "25") (name "LED_1") (class "Default")
      (node (ref "SV4") (pin "7") (pinfunction "7_7") (pintype "passive"))
    )
    (net (code "26") (name "LED_2") (class "Default")
      (node (ref "SV4") (pin "5") (pinfunction "5_5") (pintype "passive"))
    )
    (net (code "27") (name "LED_3") (class "Default")
      (node (ref "SV4") (pin "3") (pinfunction "3_3") (pintype "passive"))
    )
    (net (code "28") (name "LED_BLAU") (class "Default")
      (node (ref "SV2") (pin "9") (pinfunction "9_9") (pintype "passive"))
      (node (ref "T4") (pin "C") (pinfunction "C_C") (pintype "passive"))
    )
    (net (code "29") (name "LED_GELB") (class "Default")
      (node (ref "R_NULL_2") (pin "2") (pinfunction "2_2") (pintype "passive"))
      (node (ref "SV2") (pin "5") (pinfunction "5_5") (pintype "passive"))
    )
    (net (code "30") (name "LED_GRUEN") (class "Default")
      (node (ref "R_NULL_4") (pin "2") (pinfunction "2_2") (pintype "passive"))
      (node (ref "SV2") (pin "7") (pinfunction "7_7") (pintype "passive"))
    )
    (net (code "31") (name "LED_KICK") (class "Default")
      (node (ref "R_NULL_1") (pin "2") (pinfunction "2_2") (pintype "passive"))
      (node (ref "SV4") (pin "9") (pinfunction "9_9") (pintype "passive"))
    )
    (net (code "32") (name "LED_ROT") (class "Default")
      (node (ref "R_NULL_3") (pin "2") (pinfunction "2_2") (pintype "passive"))
      (node (ref "SV2") (pin "3") (pinfunction "3_3") (pintype "passive"))
    )
    (net (code "33") (name "MOTION") (class "Default")
      (node (ref "IC4") (pin "1") (pinfunction "OUT1_1") (pintype "passive"))
      (node (ref "IC4") (pin "5") (pinfunction "OUT2_5") (pintype "passive"))
      (node (ref "P8") (pin "3") (pinfunction "P_3") (pintype "passive"))
      (node (ref "P8") (pin "4") (pinfunction "P_4") (pintype "passive"))
      (node (ref "R15") (pin "1") (pinfunction "1_1") (pintype "passive"))
      (node (ref "R_NULL_4") (pin "1") (pinfunction "1_1") (pintype "passive"))
    )
    (net (code "34") (name "Net-(5V-PadA)") (class "Default")
      (node (ref "5V") (pin "A") (pinfunction "A_A") (pintype "passive"))
      (node (ref "R18") (pin "1") (pinfunction "1_1") (pintype "passive"))
    )
    (net (code "35") (name "Net-(12V-PadA)") (class "Default")
      (node (ref "12V") (pin "A") (pinfunction "A_A") (pintype "passive"))
      (node (ref "R28") (pin "2") (pinfunction "2_2") (pintype "passive"))
    )
    (net (code "36") (name "Net-(D1-C)") (class "Default")
      (node (ref "D1") (pin "K") (pinfunction "C_K") (pintype "passive"))
      (node (ref "D3") (pin "K") (pinfunction "C_K") (pintype "passive"))
      (node (ref "R12") (pin "1") (pinfunction "1_1") (pintype "passive"))
    )
    (net (code "37") (name "Net-(D2-C)") (class "Default")
      (node (ref "C4") (pin "2") (pinfunction "2_2") (pintype "passive"))
      (node (ref "D2") (pin "K") (pinfunction "C_K") (pintype "passive"))
      (node (ref "L2") (pin "2") (pinfunction "2_2") (pintype "passive"))
      (node (ref "U1") (pin "8") (pinfunction "VSW_8") (pintype "output"))
    )
    (net (code "38") (name "Net-(GELB-PadA)") (class "Default")
      (node (ref "GELB") (pin "A") (pinfunction "A_A") (pintype "passive"))
      (node (ref "R25") (pin "2") (pinfunction "2_2") (pintype "passive"))
    )
    (net (code "39") (name "Net-(GRÜN-PadA)") (class "Default")
      (node (ref "GRÜN") (pin "A") (pinfunction "A_A") (pintype "passive"))
      (node (ref "R27") (pin "2") (pinfunction "2_2") (pintype "passive"))
    )
    (net (code "40") (name "Net-(IC4-IN)") (class "Default")
      (node (ref "IC4") (pin "2") (pinfunction "IN_2") (pintype "input"))
      (node (ref "VR9") (pin "1") (pinfunction "C_1") (pintype "passive"))
    )
    (net (code "41") (name "Net-(KICK-PadA)") (class "Default")
      (node (ref "KICK") (pin "A") (pinfunction "A_A") (pintype "passive"))
      (node (ref "R29") (pin "2") (pinfunction "2_2") (pintype "passive"))
    )
    (net (code "42") (name "Net-(LED_BLAU-PadA)") (class "Default")
      (node (ref "LED_BLAU") (pin "A") (pinfunction "A_A") (pintype "passive"))
      (node (ref "R4") (pin "2") (pinfunction "2_2") (pintype "passive"))
    )
    (net (code "43") (name "Net-(OK1A-A)") (class "Default")
      (node (ref "OK1") (pin "1") (pinfunction "A_1") (pintype "passive"))
      (node (ref "OK1") (pin "4") (pinfunction "C_4") (pintype "passive"))
    )
    (net (code "44") (name "Net-(OK1A-C)") (class "Default")
      (node (ref "JP5") (pin "2") (pinfunction "2_2") (pintype "passive"))
      (node (ref "OK1") (pin "2") (pinfunction "C_2") (pintype "passive"))
    )
    (net (code "45") (name "Net-(OK1A-COL)") (class "Default")
      (node (ref "IC10") (pin "IN") (pinfunction "IN_IN") (pintype "input"))
      (node (ref "OK1") (pin "8") (pinfunction "COL_8") (pintype "passive"))
    )
    (net (code "46") (name "Net-(OK1A-EMIT)") (class "Default")
      (node (ref "OK1") (pin "7") (pinfunction "EMIT_7") (pintype "passive"))
      (node (ref "VR6") (pin "1") (pinfunction "C_1") (pintype "passive"))
    )
    (net (code "47") (name "Net-(OK1B-A)") (class "Default")
      (node (ref "OK1") (pin "3") (pinfunction "A_3") (pintype "passive"))
      (node (ref "R12") (pin "2") (pinfunction "2_2") (pintype "passive"))
    )
    (net (code "48") (name "Net-(OK1B-COL)") (class "Default")
      (node (ref "IC15") (pin "IN") (pinfunction "IN_IN") (pintype "input"))
      (node (ref "OK1") (pin "6") (pinfunction "COL_6") (pintype "passive"))
    )
    (net (code "49") (name "Net-(R6-Pad2)") (class "Default")
      (node (ref "R6") (pin "2") (pinfunction "2_2") (pintype "passive"))
      (node (ref "SJ1") (pin "2") (pinfunction "2_2") (pintype "passive"))
    )
    (net (code "50") (name "Net-(R7-Pad2)") (class "Default")
      (node (ref "R7") (pin "2") (pinfunction "2_2") (pintype "passive"))
      (node (ref "T4") (pin "B") (pinfunction "B_B") (pintype "passive"))
    )
    (net (code "51") (name "Net-(R26-Pad2)") (class "Default")
      (node (ref "R26") (pin "2") (pinfunction "2_2") (pintype "passive"))
      (node (ref "ROT") (pin "A") (pinfunction "A_A") (pintype "passive"))
    )
    (net (code "52") (name "Net-(RJ_1-PadP$4)") (class "Default")
      (node (ref "RJ_1") (pin "P$4") (pinfunction "P$4_P$4") (pintype "bidirectional"))
      (node (ref "RJ_2") (pin "P$4") (pinfunction "P$4_P$4") (pintype "bidirectional"))
      (node (ref "SJ2") (pin "2") (pinfunction "2_2") (pintype "passive"))
    )
    (net (code "53") (name "Net-(T1-B)") (class "Default")
      (node (ref "R5") (pin "2") (pinfunction "2_2") (pintype "passive"))
      (node (ref "T1") (pin "1") (pinfunction "B_1") (pintype "passive"))
    )
    (net (code "54") (name "Net-(T1-C)") (class "Default")
      (node (ref "T1") (pin "3") (pinfunction "C_3") (pintype "passive"))
      (node (ref "TDB-05") (pin "-") (pinfunction "2_-") (pintype "passive"))
    )
    (net (code "55") (name "Net-(T2-B)") (class "Default")
      (node (ref "R23") (pin "2") (pinfunction "2_2") (pintype "passive"))
      (node (ref "T2") (pin "1") (pinfunction "B_1") (pintype "passive"))
    )
    (net (code "56") (name "Net-(T3-B)") (class "Default")
      (node (ref "R1") (pin "2") (pinfunction "2_2") (pintype "passive"))
      (node (ref "T3") (pin "1") (pinfunction "B_1") (pintype "passive"))
    )
    (net (code "57") (name "Net-(T3-C)") (class "Default")
      (node (ref "LED_BLAU") (pin "C") (pinfunction "C_C") (pintype "passive"))
      (node (ref "R7") (pin "1") (pinfunction "1_1") (pintype "passive"))
      (node (ref "T3") (pin "3") (pinfunction "C_3") (pintype "passive"))
    )
    (net (code "58") (name "Net-(T5-B)") (class "Default")
      (node (ref "R16") (pin "2") (pinfunction "2_2") (pintype "passive"))
      (node (ref "T5") (pin "1") (pinfunction "B_1") (pintype "passive"))
    )
    (net (code "59") (name "Net-(T6-B)") (class "Default")
      (node (ref "R17") (pin "2") (pinfunction "2_2") (pintype "passive"))
      (node (ref "T6") (pin "1") (pinfunction "B_1") (pintype "passive"))
    )
    (net (code "60") (name "Net-(T7-B)") (class "Default")
      (node (ref "R15") (pin "2") (pinfunction "2_2") (pintype "passive"))
      (node (ref "T7") (pin "1") (pinfunction "B_1") (pintype "passive"))
    )
    (net (code "61") (name "Net-(U$1-RS)") (class "Default")
      (node (ref "R31") (pin "2") (pinfunction "2_2") (pintype "passive"))
      (node (ref "U$1") (pin "8") (pinfunction "RS_8") (pintype "input"))
    )
    (net (code "62") (name "Net-(U$2-AREF)") (class "Default")
      (node (ref "C14") (pin "2") (pinfunction "2_2") (pintype "passive"))
      (node (ref "U$2") (pin "21") (pinfunction "AREF_21") (pintype "bidirectional"))
    )
    (net (code "63") (name "Net-(U$2-PE1(XTAL1))") (class "Default")
      (node (ref "C11") (pin "2") (pinfunction "2_2") (pintype "passive"))
      (node (ref "Q1") (pin "1") (pinfunction "1_1") (pintype "passive"))
      (node (ref "U$2") (pin "10") (pinfunction "PE1(XTAL1)_10") (pintype "bidirectional"))
    )
    (net (code "64") (name "Net-(U$2-PE2(XTAL2))") (class "Default")
      (node (ref "C10") (pin "2") (pinfunction "2_2") (pintype "passive"))
      (node (ref "Q1") (pin "2") (pinfunction "2_2") (pintype "passive"))
      (node (ref "U$2") (pin "11") (pinfunction "PE2(XTAL2)_11") (pintype "bidirectional"))
    )
    (net (code "65") (name "Net-(U1-CB)") (class "Default")
      (node (ref "C4") (pin "1") (pinfunction "1_1") (pintype "passive"))
      (node (ref "U1") (pin "1") (pinfunction "CB_1") (pintype "input"))
    )
    (net (code "66") (name "Net-(U1-VIN)") (class "Default")
      (node (ref "C2") (pin "+") (pinfunction "+_+") (pintype "passive"))
      (node (ref "F1") (pin "2") (pinfunction "2_2") (pintype "passive"))
      (node (ref "U1") (pin "7") (pinfunction "VIN_7") (pintype "power_in"))
    )
    (net (code "67") (name "Net-(VR7-A)") (class "Default")
      (node (ref "JP2") (pin "2") (pinfunction "2_2") (pintype "passive"))
      (node (ref "VR7") (pin "3") (pinfunction "A_3") (pintype "passive"))
    )
    (net (code "68") (name "Net-(VR7-C)") (class "Default")
      (node (ref "IC11") (pin "IN") (pinfunction "IN_IN") (pintype "input"))
      (node (ref "VR7") (pin "1") (pinfunction "C_1") (pintype "passive"))
    )
    (net (code "69") (name "Net-(VR7-R)") (class "Default")
      (node (ref "R36") (pin "2") (pinfunction "2_2") (pintype "passive"))
      (node (ref "R37") (pin "1") (pinfunction "1_1") (pintype "passive"))
      (node (ref "VR7") (pin "2") (pinfunction "R_2") (pintype "passive"))
    )
    (net (code "70") (name "Net-(VR8-A)") (class "Default")
      (node (ref "JP3") (pin "2") (pinfunction "2_2") (pintype "passive"))
      (node (ref "VR8") (pin "3") (pinfunction "A_3") (pintype "passive"))
    )
    (net (code "71") (name "Net-(VR8-C)") (class "Default")
      (node (ref "IC12") (pin "IN") (pinfunction "IN_IN") (pintype "input"))
      (node (ref "VR8") (pin "1") (pinfunction "C_1") (pintype "passive"))
    )
    (net (code "72") (name "Net-(VR8-R)") (class "Default")
      (node (ref "R38") (pin "2") (pinfunction "2_2") (pintype "passive"))
      (node (ref "R39") (pin "1") (pinfunction "1_1") (pintype "passive"))
      (node (ref "VR8") (pin "2") (pinfunction "R_2") (pintype "passive"))
    )
    (net (code "73") (name "Net-(VR9-A)") (class "Default")
      (node (ref "JP4") (pin "2") (pinfunction "2_2") (pintype "passive"))
      (node (ref "VR9") (pin "3") (pinfunction "A_3") (pintype "passive"))
    )
    (net (code "74") (name "Net-(VR9-R)") (class "Default")
      (node (ref "R40") (pin "2") (pinfunction "2_2") (pintype "passive"))
      (node (ref "R41") (pin "1") (pinfunction "1_1") (pintype "passive"))
      (node (ref "VR9") (pin "2") (pinfunction "R_2") (pintype "passive"))
    )
    (net (code "75") (name "Net-(VR10-C)") (class "Default")
      (node (ref "R30") (pin "2") (pinfunction "2_2") (pintype "passive"))
      (node (ref "R35") (pin "1") (pinfunction "1_1") (pintype "passive"))
      (node (ref "VR10") (pin "1") (pinfunction "C_1") (pintype "passive"))
      (node (ref "VR6") (pin "2") (pinfunction "R_2") (pintype "passive"))
    )
    (net (code "76") (name "Net-(VR10-R)") (class "Default")
      (node (ref "R45") (pin "1") (pinfunction "1_1") (pintype "passive"))
      (node (ref "R46") (pin "2") (pinfunction "2_2") (pintype "passive"))
      (node (ref "VR10") (pin "2") (pinfunction "R_2") (pintype "passive"))
    )
    (net (code "77") (name "RST") (class "Default")
      (node (ref "ISP") (pin "5") (pinfunction "5_5") (pintype "passive"))
      (node (ref "U$2") (pin "31") (pinfunction "PE0(RESET)_31") (pintype "input"))
    )
    (net (code "78") (name "RXCAN") (class "Default")
      (node (ref "U$1") (pin "4") (pinfunction "RXD_4") (pintype "output"))
      (node (ref "U$2") (pin "7") (pinfunction "(RXCAN)PC3_7") (pintype "bidirectional"))
    )
    (net (code "79") (name "SPEAKER") (class "Default")
      (node (ref "R5") (pin "1") (pinfunction "1_1") (pintype "passive"))
      (node (ref "U$2") (pin "29") (pinfunction "PD0_29") (pintype "bidirectional"))
    )
    (net (code "80") (name "SW_1") (class "Default")
      (node (ref "SV4") (pin "8") (pinfunction "8_8") (pintype "passive"))
    )
    (net (code "81") (name "SW_1{slash}SCK_A") (class "Default")
      (node (ref "ISP") (pin "7") (pinfunction "7_7") (pintype "passive"))
      (node (ref "U$2") (pin "12") (pinfunction "(RXD)PD4_12") (pintype "bidirectional"))
    )
    (net (code "82") (name "SW_2") (class "Default")
      (node (ref "SV4") (pin "6") (pinfunction "6_6") (pintype "passive"))
    )
    (net (code "83") (name "SW_2{slash}MOSI_A") (class "Default")
      (node (ref "ISP") (pin "1") (pinfunction "1_1") (pintype "passive"))
      (node (ref "U$2") (pin "2") (pinfunction "(MOSI_A/TXD)PD3_2") (pintype "bidirectional"))
    )
    (net (code "84") (name "SW_3") (class "Default")
      (node (ref "SV4") (pin "4") (pinfunction "4_4") (pintype "passive"))
    )
    (net (code "85") (name "SW_3{slash}MISO_A") (class "Default")
      (node (ref "ISP") (pin "9") (pinfunction "9_9") (pintype "passive"))
      (node (ref "U$2") (pin "1") (pinfunction "(MISO_A)PD2_1") (pintype "bidirectional"))
    )
    (net (code "86") (name "SW_12V") (class "Default")
      (node (ref "JP5") (pin "1") (pinfunction "1_1") (pintype "passive"))
      (node (ref "SV2") (pin "4") (pinfunction "4_4") (pintype "passive"))
      (node (ref "U$2") (pin "15") (pinfunction "PD7_15") (pintype "bidirectional"))
    )
    (net (code "87") (name "SW_AKT") (class "Default")
      (node (ref "JP2") (pin "1") (pinfunction "1_1") (pintype "passive"))
      (node (ref "SJ3") (pin "1") (pinfunction "1_1") (pintype "passive"))
      (node (ref "SV2") (pin "6") (pinfunction "6_6") (pintype "passive"))
      (node (ref "U$2") (pin "8") (pinfunction "PB0_8") (pintype "bidirectional"))
    )
    (net (code "88") (name "SW_BLAU") (class "Default")
      (node (ref "SV2") (pin "10") (pinfunction "10_10") (pintype "passive"))
      (node (ref "U$2") (pin "3") (pinfunction "PC1_3") (pintype "bidirectional"))
    )
    (net (code "89") (name "SW_KICK") (class "Default")
      (node (ref "JP3") (pin "1") (pinfunction "1_1") (pintype "passive"))
      (node (ref "SJ3") (pin "2") (pinfunction "2_2") (pintype "passive"))
      (node (ref "SV4") (pin "10") (pinfunction "10_10") (pintype "passive"))
      (node (ref "U$2") (pin "25") (pinfunction "PC7_25") (pintype "bidirectional"))
    )
    (net (code "90") (name "SW_MOT") (class "Default")
      (node (ref "JP4") (pin "1") (pinfunction "1_1") (pintype "passive"))
      (node (ref "SV2") (pin "8") (pinfunction "8_8") (pintype "passive"))
      (node (ref "U$2") (pin "9") (pinfunction "PB1_9") (pintype "bidirectional"))
    )
    (net (code "91") (name "TXCAN") (class "Default")
      (node (ref "U$1") (pin "1") (pinfunction "TXD_1") (pintype "input"))
      (node (ref "U$2") (pin "6") (pinfunction "(TXCAN)PC2_6") (pintype "bidirectional"))
    )
    (net (code "92") (name "unconnected-(ISP-Pad3)") (class "Default")
      (node (ref "ISP") (pin "3") (pinfunction "3_3") (pintype "passive"))
    )
    (net (code "93") (name "unconnected-(U$1-VREF-Pad5)") (class "Default")
      (node (ref "U$1") (pin "5") (pinfunction "VREF_5") (pintype "output"))
    )
    (net (code "94") (name "unconnected-(U$2-PD1-Pad32)") (class "Default")
      (node (ref "U$2") (pin "32") (pinfunction "PD1_32") (pintype "bidirectional"))
    )
    (net (code "95") (name "unconnected-(U1-NC-Pad3)") (class "Default")
      (node (ref "U1") (pin "3") (pinfunction "NC_3") (pintype "no_connect"))
    )
    (net (code "96") (name "unconnected-(U1-NC_2-Pad2)") (class "Default")
      (node (ref "U1") (pin "2") (pinfunction "NC_2_2") (pintype "no_connect"))
    )
    (net (code "97") (name "unconnected-(U1-ON{slash}~{OFF}-Pad5)") (class "Default")
      (node (ref "U1") (pin "5") (pinfunction "ON/~{OFF}_5") (pintype "input"))
    )
  )
)
